# 11-mppt.net
KiCad netlist of a schematic drawn in Altium Designer
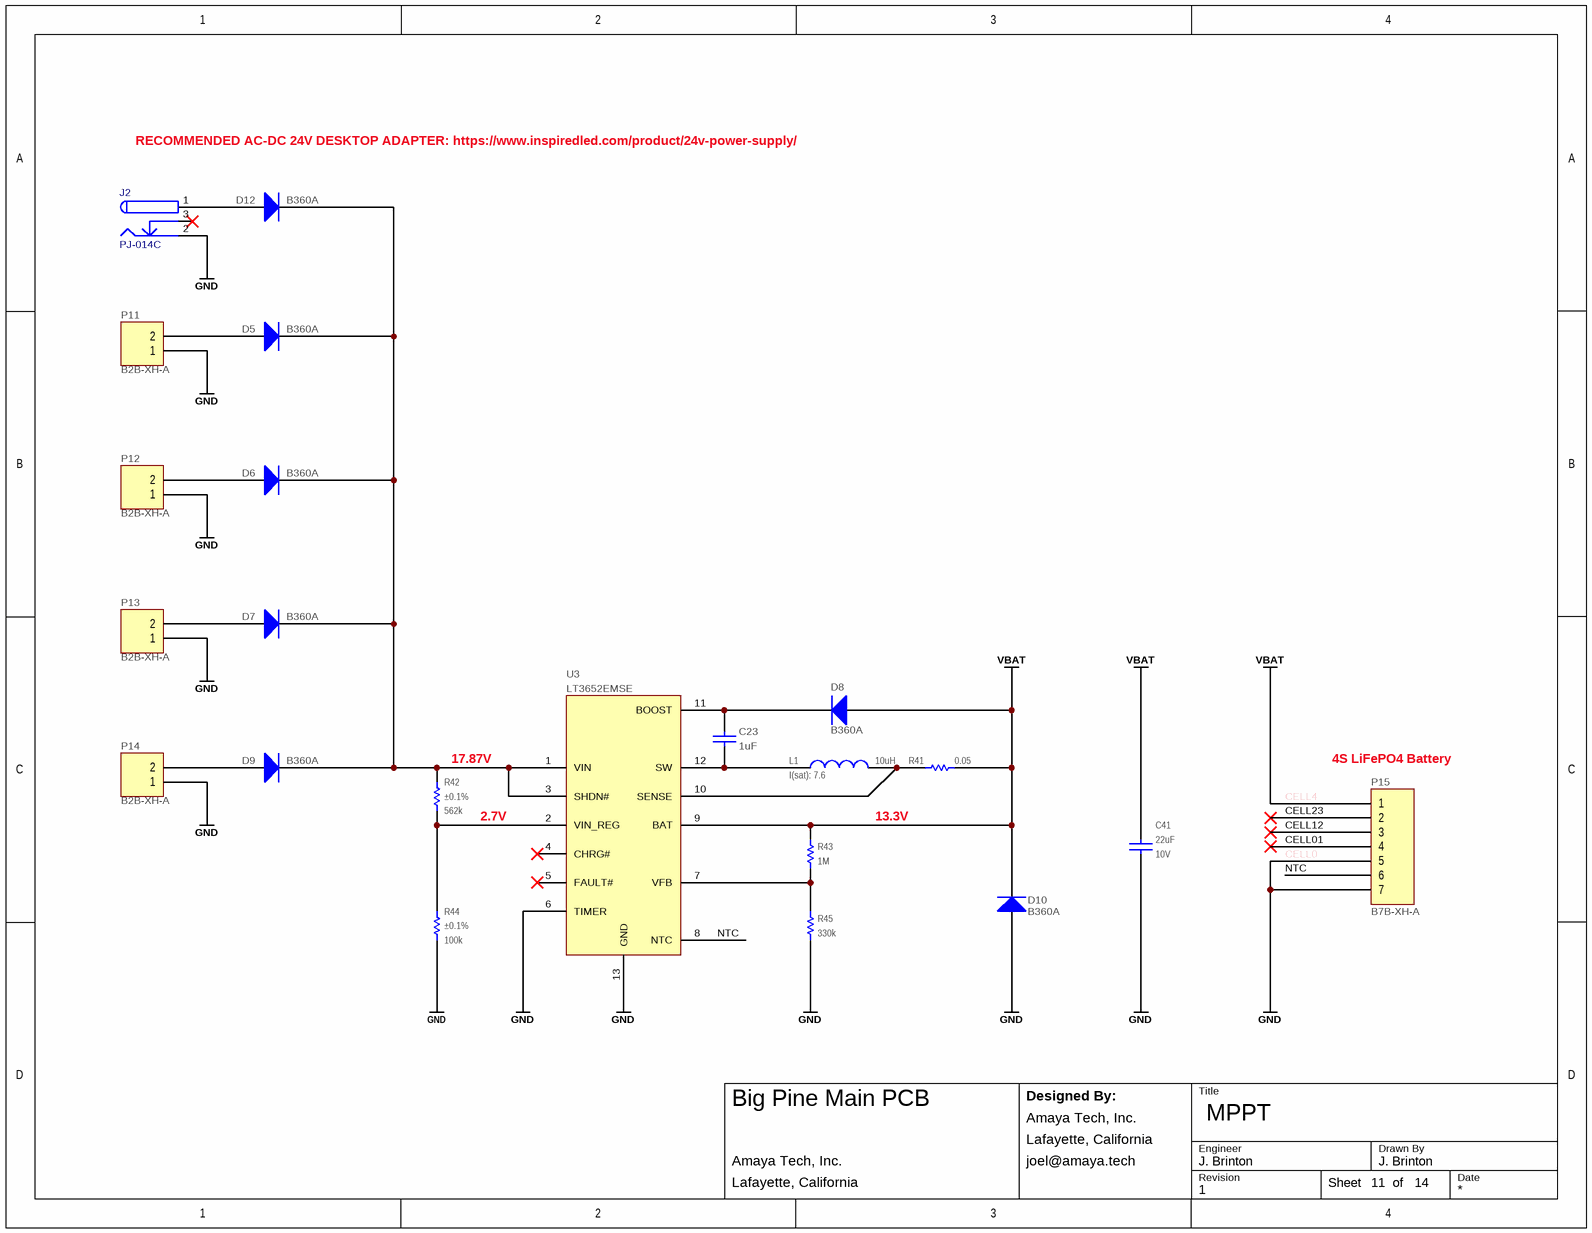
[diagram p0: 11-mppt.SchDoc]

(export (version "E")
  (design (tool "Eeschema 10.0.6"))
  (components
    (comp (ref "C23")
      (value "1uF")
      (footprint "CAPC200X125X145L45N")
      (description "Ceramic Capacitor 1uF ±10% 25V X7R 0805")
      (fields (field (name "MANUFACTURER") "Taiyo Yuden") (field (name "TOLERANCE") "±10%"))
      (libsource (lib "capacitors") (part "CAP"))
    )
    (comp (ref "C41")
      (value "22uF")
      (footprint "CAPC200X125X145L45N")
      (description "Ceramic Capacitor 22uF ±20% 10V X7S 0805")
      (fields
        (field (name "MANUFACTURER") "TDK")
        (field (name "TOLERANCE") "±20%")
        (field (name "VOLTAGE") "10V")
      )
      (libsource (lib "generic") (part "CAP"))
    )
    (comp (ref "D5")
      (value "B360A")
      (footprint "SMA")
      (description "DIODE SCHOTTKY 60V 3A SMA")
      (fields (field (name "MANUFACTURER") "Diodes Inc"))
      (libsource (lib "diodes_inc") (part "D360A"))
    )
    (comp (ref "D6")
      (value "B360A")
      (footprint "SMA")
      (description "DIODE SCHOTTKY 60V 3A SMA")
      (fields (field (name "MANUFACTURER") "Diodes Inc"))
      (libsource (lib "diodes_inc") (part "D360A"))
    )
    (comp (ref "D7")
      (value "B360A")
      (footprint "SMA")
      (description "DIODE SCHOTTKY 60V 3A SMA")
      (fields (field (name "MANUFACTURER") "Diodes Inc"))
      (libsource (lib "diodes_inc") (part "D360A"))
    )
    (comp (ref "D8")
      (value "B360A")
      (footprint "SMA")
      (description "DIODE SCHOTTKY 60V 3A SMA")
      (fields (field (name "MANUFACTURER") "Diodes Inc"))
      (libsource (lib "diodes_inc") (part "D360A"))
    )
    (comp (ref "D9")
      (value "B360A")
      (footprint "SMA")
      (description "DIODE SCHOTTKY 60V 3A SMA")
      (fields (field (name "MANUFACTURER") "Diodes Inc"))
      (libsource (lib "diodes_inc") (part "D360A"))
    )
    (comp (ref "D10")
      (value "B360A")
      (footprint "SMA")
      (description "DIODE SCHOTTKY 60V 3A SMA")
      (fields (field (name "MANUFACTURER") "Diodes Inc"))
      (libsource (lib "diodes_inc") (part "D360A"))
    )
    (comp (ref "D12")
      (value "B360A")
      (footprint "SMA")
      (description "DIODE SCHOTTKY 60V 3A SMA")
      (fields (field (name "MANUFACTURER") "Diodes Inc"))
      (libsource (lib "diodes_inc") (part "D360A"))
    )
    (comp (ref "J2")
      (value "PJ-014C")
      (footprint "PJ-014C")
      (description "DC Power Jack")
      (fields (field (name "MANUFACTURER") "CUI"))
      (libsource (lib "cui") (part "PJ-014C"))
    )
    (comp (ref "L1")
      (value "10uH")
      (footprint "coilcraft:XAL6030")
      (description "Shielded Power Inductor 10uH, 7.6A")
      (fields
        (field (name "MANUFACTURER") "Coilcraft")
        (field (name "I(SAT)") "7.6")
        (field (name "Comment") "XAL6030-103ME")
      )
      (libsource (lib "generic") (part "INDUCTOR"))
    )
    (comp (ref "P11")
      (value "B2B-XH-A")
      (footprint "jst:B2B-XH-A")
      (description "Header, 2-Pin")
      (fields (field (name "MANUFACTURER") "JST"))
      (libsource (lib "Miscellaneous Connectors") (part "Header 2"))
    )
    (comp (ref "P12")
      (value "B2B-XH-A")
      (footprint "jst:B2B-XH-A")
      (description "Header, 2-Pin")
      (fields (field (name "MANUFACTURER") "JST"))
      (libsource (lib "Miscellaneous Connectors") (part "Header 2"))
    )
    (comp (ref "P13")
      (value "B2B-XH-A")
      (footprint "jst:B2B-XH-A")
      (description "Header, 2-Pin")
      (fields (field (name "MANUFACTURER") "JST"))
      (libsource (lib "Miscellaneous Connectors") (part "Header 2"))
    )
    (comp (ref "P14")
      (value "B2B-XH-A")
      (footprint "jst:B2B-XH-A")
      (description "Header, 2-Pin")
      (fields (field (name "MANUFACTURER") "JST"))
      (libsource (lib "Miscellaneous Connectors") (part "Header 2"))
    )
    (comp (ref "P15")
      (value "B7B-XH-A")
      (footprint "B7B-XH-A")
      (description "Header, 7-Pin")
      (fields (field (name "MANUFACTURER") "JST"))
      (libsource (lib "Miscellaneous Connectors") (part "Header 7"))
    )
    (comp (ref "R41")
      (value "0.05")
      (footprint "RESC2012X70N")
      (description "Thick Film Resistor 0.05 ±1% 0805")
      (fields (field (name "MANUFACTURER") "Panasonic") (field (name "TOLERANCE") "±1%"))
      (libsource (lib "Graviton") (part "RES 0402"))
    )
    (comp (ref "R42")
      (value "562k")
      (footprint "RESC2012X70N")
      (description "Thin Film Resistor 562k ±0.1% 0.125W 100V 0805")
      (fields
        (field (name "TOLERANCE") "±0.1%")
        (field (name "MANUFACTURER") "Panasonic")
        (field (name "VOLTAGE") "100")
      )
      (libsource (lib "generic") (part "RES"))
    )
    (comp (ref "R43")
      (value "1M")
      (footprint "RESC2012X70N")
      (description "Thick Film Resistor 1M ±1% 0805")
      (fields (field (name "MANUFACTURER") "Panasonic") (field (name "TOLERANCE") "±1%"))
      (libsource (lib "Graviton") (part "RES 0402"))
    )
    (comp (ref "R44")
      (value "100k")
      (footprint "RESC2012X70N")
      (description "Thin Film Resistor 100k ±0.1% 0.125W 100V 0805")
      (fields
        (field (name "TOLERANCE") "±0.1%")
        (field (name "MANUFACTURER") "Panasonic")
        (field (name "VOLTAGE") "100")
      )
      (libsource (lib "generic") (part "RES"))
    )
    (comp (ref "R45")
      (value "330k")
      (footprint "RESC2012X70N")
      (description "Thick Film Resistor 330k ±1% 0805")
      (fields (field (name "MANUFACTURER") "Panasonic") (field (name "TOLERANCE") "±1%"))
      (libsource (lib "Graviton") (part "RES 0402"))
    )
    (comp (ref "U3")
      (value "LT3652EMSE")
      (footprint "linear:12-MSOP-EP")
      (description "Power Tracking 2A Battery Charger for Solar Power")
      (fields (field (name "MANUFACTURER") "Analog Devices"))
      (libsource (lib "linear") (part "LT3652EMSE"))
    )
  )
  (nets
    (net (code "1") (name "/CELL01") (class "Default")
      (node (ref "P15") (pin "4") (pinfunction "4_4") (pintype "passive+no_connect"))
    )
    (net (code "2") (name "/CELL12") (class "Default")
      (node (ref "P15") (pin "3") (pinfunction "3_3") (pintype "passive+no_connect"))
    )
    (net (code "3") (name "/CELL23") (class "Default")
      (node (ref "P15") (pin "2") (pinfunction "2_2") (pintype "passive+no_connect"))
    )
    (net (code "4") (name "/NTC") (class "Default")
      (node (ref "P15") (pin "6") (pinfunction "6_6") (pintype "passive"))
      (node (ref "U3") (pin "8") (pinfunction "NTC_8") (pintype "passive"))
    )
    (net (code "5") (name "GND") (class "Default")
      (node (ref "C41") (pin "1") (pinfunction "1_1") (pintype "passive"))
      (node (ref "D10") (pin "1") (pinfunction "A_1") (pintype "power_in"))
      (node (ref "J2") (pin "2") (pinfunction "2_2") (pintype "power_in"))
      (node (ref "P11") (pin "1") (pinfunction "1_1") (pintype "passive"))
      (node (ref "P12") (pin "1") (pinfunction "1_1") (pintype "passive"))
      (node (ref "P13") (pin "1") (pinfunction "1_1") (pintype "passive"))
      (node (ref "P14") (pin "1") (pinfunction "1_1") (pintype "passive"))
      (node (ref "P15") (pin "5") (pinfunction "5_5") (pintype "passive"))
      (node (ref "P15") (pin "7") (pinfunction "7_7") (pintype "passive"))
      (node (ref "R44") (pin "1") (pinfunction "1_1") (pintype "passive"))
      (node (ref "R45") (pin "1") (pinfunction "1_1") (pintype "passive"))
      (node (ref "U3") (pin "13") (pinfunction "GND_13") (pintype "passive"))
      (node (ref "U3") (pin "6") (pinfunction "TIMER_6") (pintype "passive"))
    )
    (net (code "6") (name "Net-(D5-A)") (class "Default")
      (node (ref "D5") (pin "1") (pinfunction "A_1") (pintype "power_in"))
      (node (ref "P11") (pin "2") (pinfunction "2_2") (pintype "passive"))
    )
    (net (code "7") (name "Net-(D6-A)") (class "Default")
      (node (ref "D6") (pin "1") (pinfunction "A_1") (pintype "power_in"))
      (node (ref "P12") (pin "2") (pinfunction "2_2") (pintype "passive"))
    )
    (net (code "8") (name "Net-(D7-A)") (class "Default")
      (node (ref "D7") (pin "1") (pinfunction "A_1") (pintype "power_in"))
      (node (ref "P13") (pin "2") (pinfunction "2_2") (pintype "passive"))
    )
    (net (code "9") (name "Net-(D8-K)") (class "Default")
      (node (ref "C23") (pin "1") (pinfunction "1_1") (pintype "passive"))
      (node (ref "D8") (pin "2") (pinfunction "K_2") (pintype "passive"))
      (node (ref "U3") (pin "11") (pinfunction "BOOST_11") (pintype "passive"))
    )
    (net (code "10") (name "Net-(D9-A)") (class "Default")
      (node (ref "D9") (pin "1") (pinfunction "A_1") (pintype "power_in"))
      (node (ref "P14") (pin "2") (pinfunction "2_2") (pintype "passive"))
    )
    (net (code "11") (name "Net-(D12-A)") (class "Default")
      (node (ref "D12") (pin "1") (pinfunction "A_1") (pintype "power_in"))
      (node (ref "J2") (pin "1") (pinfunction "1_1") (pintype "power_in"))
    )
    (net (code "12") (name "Net-(D12-K)") (class "Default")
      (node (ref "D12") (pin "2") (pinfunction "K_2") (pintype "passive"))
      (node (ref "D5") (pin "2") (pinfunction "K_2") (pintype "passive"))
      (node (ref "D6") (pin "2") (pinfunction "K_2") (pintype "passive"))
      (node (ref "D7") (pin "2") (pinfunction "K_2") (pintype "passive"))
      (node (ref "D9") (pin "2") (pinfunction "K_2") (pintype "passive"))
      (node (ref "R42") (pin "2") (pinfunction "2_2") (pintype "passive"))
      (node (ref "U3") (pin "1") (pinfunction "VIN_1") (pintype "passive"))
      (node (ref "U3") (pin "3") (pinfunction "SHDN#_3") (pintype "passive"))
    )
    (net (code "13") (name "Net-(U3-SENSE)") (class "Default")
      (node (ref "L1") (pin "2") (pinfunction "2_2") (pintype "passive"))
      (node (ref "R41") (pin "2") (pinfunction "2_2") (pintype "passive"))
      (node (ref "U3") (pin "10") (pinfunction "SENSE_10") (pintype "passive"))
    )
    (net (code "14") (name "Net-(U3-SW)") (class "Default")
      (node (ref "C23") (pin "2") (pinfunction "2_2") (pintype "passive"))
      (node (ref "L1") (pin "1") (pinfunction "1_1") (pintype "passive"))
      (node (ref "U3") (pin "12") (pinfunction "SW_12") (pintype "passive"))
    )
    (net (code "15") (name "Net-(U3-VFB)") (class "Default")
      (node (ref "R43") (pin "1") (pinfunction "1_1") (pintype "passive"))
      (node (ref "R45") (pin "2") (pinfunction "2_2") (pintype "passive"))
      (node (ref "U3") (pin "7") (pinfunction "VFB_7") (pintype "passive"))
    )
    (net (code "16") (name "Net-(U3-VIN_REG)") (class "Default")
      (node (ref "R42") (pin "1") (pinfunction "1_1") (pintype "passive"))
      (node (ref "R44") (pin "2") (pinfunction "2_2") (pintype "passive"))
      (node (ref "U3") (pin "2") (pinfunction "VIN_REG_2") (pintype "passive"))
    )
    (net (code "17") (name "VBAT") (class "Default")
      (node (ref "C41") (pin "2") (pinfunction "2_2") (pintype "passive"))
      (node (ref "D10") (pin "2") (pinfunction "K_2") (pintype "passive"))
      (node (ref "D8") (pin "1") (pinfunction "A_1") (pintype "power_in"))
      (node (ref "P15") (pin "1") (pinfunction "1_1") (pintype "passive"))
      (node (ref "R41") (pin "1") (pinfunction "1_1") (pintype "passive"))
      (node (ref "R43") (pin "2") (pinfunction "2_2") (pintype "passive"))
      (node (ref "U3") (pin "9") (pinfunction "BAT_9") (pintype "passive"))
    )
    (net (code "18") (name "unconnected-(J2-Pad3)") (class "Default")
      (node (ref "J2") (pin "3") (pinfunction "3_3") (pintype "power_in+no_connect"))
    )
    (net (code "19") (name "unconnected-(U3-CHRG#-Pad4)") (class "Default")
      (node (ref "U3") (pin "4") (pinfunction "CHRG#_4") (pintype "passive+no_connect"))
    )
    (net (code "20") (name "unconnected-(U3-FAULT#-Pad5)") (class "Default")
      (node (ref "U3") (pin "5") (pinfunction "FAULT#_5") (pintype "passive+no_connect"))
    )
  )
)
